# Sheet1.net
KiCad netlist of a schematic drawn in Altium Designer
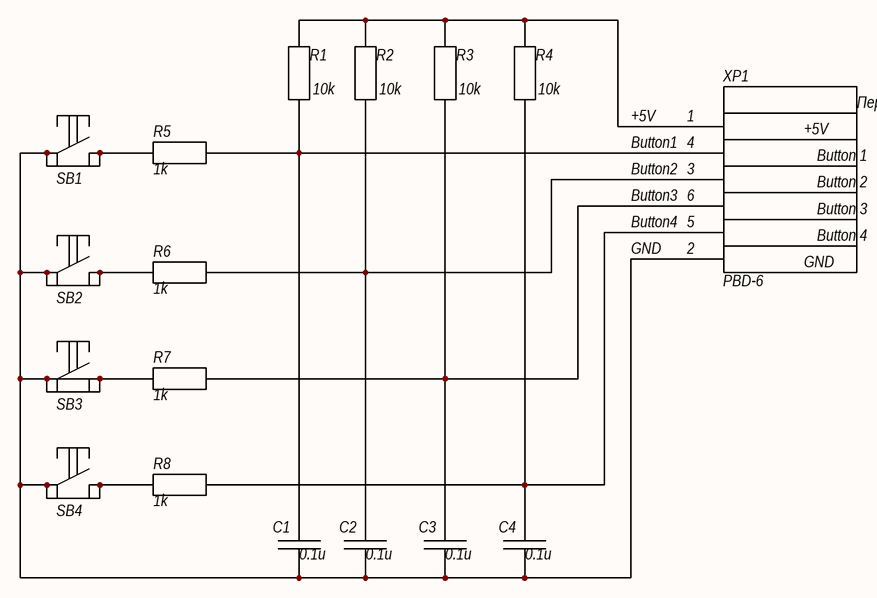
[diagram p0: Sheet1.SchDoc]

(export (version "E")
  (design (tool "Eeschema 10.0.6"))
  (components
    (comp (ref "C1")
      (value "0.1u")
      (footprint "MyLibrary:Cap 0805")
      (libsource (lib "MyLibrary") (part "Capacitor"))
    )
    (comp (ref "C2")
      (value "0.1u")
      (footprint "MyLibrary:Cap 0805")
      (libsource (lib "MyLibrary") (part "Capacitor"))
    )
    (comp (ref "C3")
      (value "0.1u")
      (footprint "MyLibrary:Cap 0805")
      (libsource (lib "MyLibrary") (part "Capacitor"))
    )
    (comp (ref "C4")
      (value "0.1u")
      (footprint "MyLibrary:Cap 0805")
      (libsource (lib "MyLibrary") (part "Capacitor"))
    )
    (comp (ref "R1")
      (value "10k")
      (footprint "MyLibrary:Res 0805")
      (libsource (lib "MyLibrary") (part "Resistor"))
    )
    (comp (ref "R2")
      (value "10k")
      (footprint "MyLibrary:Res 0805")
      (libsource (lib "MyLibrary") (part "Resistor"))
    )
    (comp (ref "R3")
      (value "10k")
      (footprint "MyLibrary:Res 0805")
      (libsource (lib "MyLibrary") (part "Resistor"))
    )
    (comp (ref "R4")
      (value "10k")
      (footprint "MyLibrary:Res 0805")
      (libsource (lib "MyLibrary") (part "Resistor"))
    )
    (comp (ref "R5") (value "1k") (footprint "MyLibrary:Res 0805") (libsource (lib "") (part "Resistor_1")))
    (comp (ref "R6") (value "1k") (footprint "MyLibrary:Res 0805") (libsource (lib "") (part "Resistor_1")))
    (comp (ref "R7") (value "1k") (footprint "MyLibrary:Res 0805") (libsource (lib "") (part "Resistor_1")))
    (comp (ref "R8") (value "1k") (footprint "MyLibrary:Res 0805") (libsource (lib "") (part "Resistor_1")))
    (comp (ref "SB1")
      (value "Switch")
      (footprint "MyLibrary:Switch Tact")
      (libsource (lib "MyLibrary") (part "Switch Tact"))
    )
    (comp (ref "SB2")
      (value "Switch")
      (footprint "MyLibrary:Switch Tact")
      (libsource (lib "MyLibrary") (part "Switch Tact"))
    )
    (comp (ref "SB3")
      (value "Switch")
      (footprint "MyLibrary:Switch Tact")
      (libsource (lib "MyLibrary") (part "Switch Tact"))
    )
    (comp (ref "SB4")
      (value "Switch")
      (footprint "MyLibrary:Switch Tact")
      (libsource (lib "MyLibrary") (part "Switch Tact"))
    )
    (comp (ref "XP1")
      (value "PBD-6")
      (footprint "MyLibrary:PBD-6")
      (libsource (lib "MyLibrary") (part "PBD-6"))
    )
  )
  (nets
    (net (code "1") (name "/+5V") (class "Default")
      (node (ref "R1") (pin "2") (pintype "power_in"))
      (node (ref "R2") (pin "2") (pintype "power_in"))
      (node (ref "R3") (pin "2") (pintype "power_in"))
      (node (ref "R4") (pin "2") (pintype "power_in"))
      (node (ref "XP1") (pin "1") (pinfunction "1_1") (pintype "power_in"))
    )
    (net (code "2") (name "/Button1") (class "Default")
      (node (ref "C1") (pin "1") (pintype "power_in"))
      (node (ref "R1") (pin "1") (pintype "power_in"))
      (node (ref "R5") (pin "2") (pintype "power_in"))
      (node (ref "XP1") (pin "4") (pinfunction "4_4") (pintype "power_in"))
    )
    (net (code "3") (name "/Button2") (class "Default")
      (node (ref "C2") (pin "1") (pintype "power_in"))
      (node (ref "R2") (pin "1") (pintype "power_in"))
      (node (ref "R6") (pin "2") (pintype "power_in"))
      (node (ref "XP1") (pin "3") (pinfunction "3_3") (pintype "power_in"))
    )
    (net (code "4") (name "/Button3") (class "Default")
      (node (ref "C3") (pin "1") (pintype "power_in"))
      (node (ref "R3") (pin "1") (pintype "power_in"))
      (node (ref "R7") (pin "2") (pintype "power_in"))
      (node (ref "XP1") (pin "6") (pinfunction "6_6") (pintype "power_in"))
    )
    (net (code "5") (name "/Button4") (class "Default")
      (node (ref "C4") (pin "1") (pintype "power_in"))
      (node (ref "R4") (pin "1") (pintype "power_in"))
      (node (ref "R8") (pin "2") (pintype "power_in"))
      (node (ref "XP1") (pin "5") (pinfunction "5_5") (pintype "power_in"))
    )
    (net (code "6") (name "/GND") (class "Default")
      (node (ref "C1") (pin "2") (pintype "power_in"))
      (node (ref "C2") (pin "2") (pintype "power_in"))
      (node (ref "C3") (pin "2") (pintype "power_in"))
      (node (ref "C4") (pin "2") (pintype "power_in"))
      (node (ref "R7") (pin "1") (pintype "power_in"))
      (node (ref "SB1") (pin "1") (pinfunction "1_1") (pintype "power_in"))
      (node (ref "SB1") (pin "3") (pinfunction "3_3") (pintype "power_in"))
      (node (ref "SB2") (pin "1") (pinfunction "1_1") (pintype "power_in"))
      (node (ref "SB2") (pin "3") (pinfunction "3_3") (pintype "power_in"))
      (node (ref "SB3") (pin "1") (pinfunction "1_1") (pintype "power_in"))
      (node (ref "SB3") (pin "2") (pinfunction "2_2") (pintype "power_in"))
      (node (ref "SB3") (pin "3") (pinfunction "3_3") (pintype "power_in"))
      (node (ref "SB3") (pin "4") (pinfunction "4_4") (pintype "power_in"))
      (node (ref "SB4") (pin "1") (pinfunction "1_1") (pintype "power_in"))
      (node (ref "SB4") (pin "3") (pinfunction "3_3") (pintype "power_in"))
      (node (ref "XP1") (pin "2") (pinfunction "2_2") (pintype "power_in"))
    )
    (net (code "7") (name "Net-(R5-Pad1)") (class "Default")
      (node (ref "R5") (pin "1") (pintype "power_in"))
      (node (ref "SB1") (pin "2") (pinfunction "2_2") (pintype "power_in"))
      (node (ref "SB1") (pin "4") (pinfunction "4_4") (pintype "power_in"))
    )
    (net (code "8") (name "Net-(R6-Pad1)") (class "Default")
      (node (ref "R6") (pin "1") (pintype "power_in"))
      (node (ref "SB2") (pin "2") (pinfunction "2_2") (pintype "power_in"))
      (node (ref "SB2") (pin "4") (pinfunction "4_4") (pintype "power_in"))
    )
    (net (code "9") (name "Net-(R8-Pad1)") (class "Default")
      (node (ref "R8") (pin "1") (pintype "power_in"))
      (node (ref "SB4") (pin "2") (pinfunction "2_2") (pintype "power_in"))
      (node (ref "SB4") (pin "4") (pinfunction "4_4") (pintype "power_in"))
    )
  )
)
